# BillyBassShield.net
KiCad netlist of a schematic drawn in EAGLE
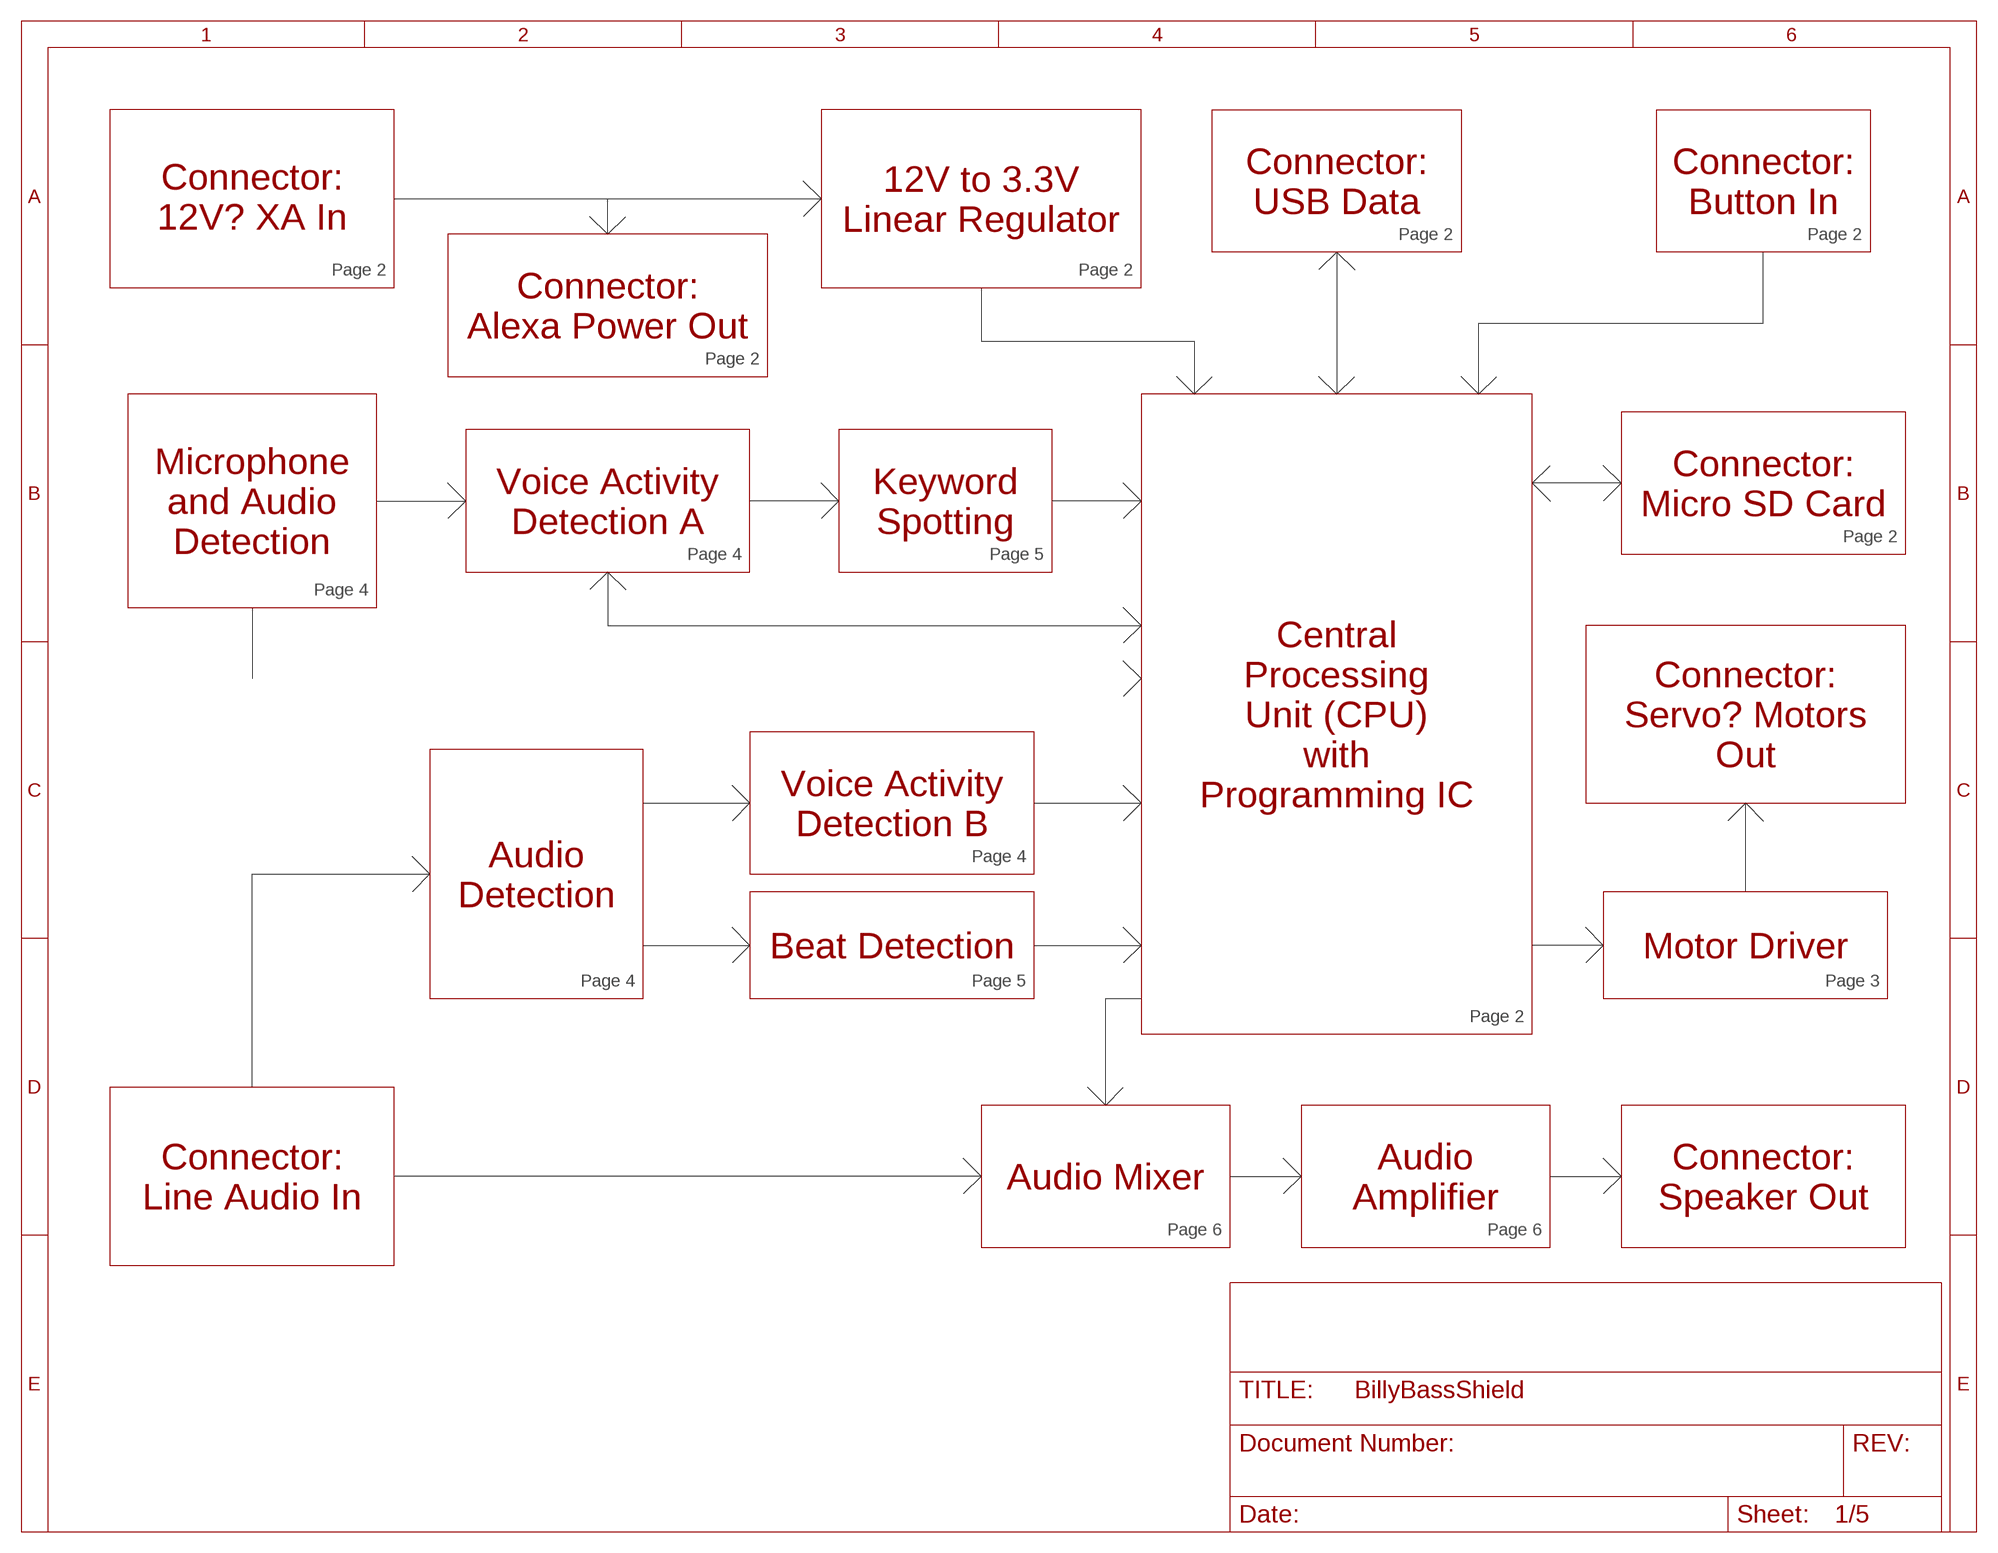
[diagram p0: schematic, sheet 1]
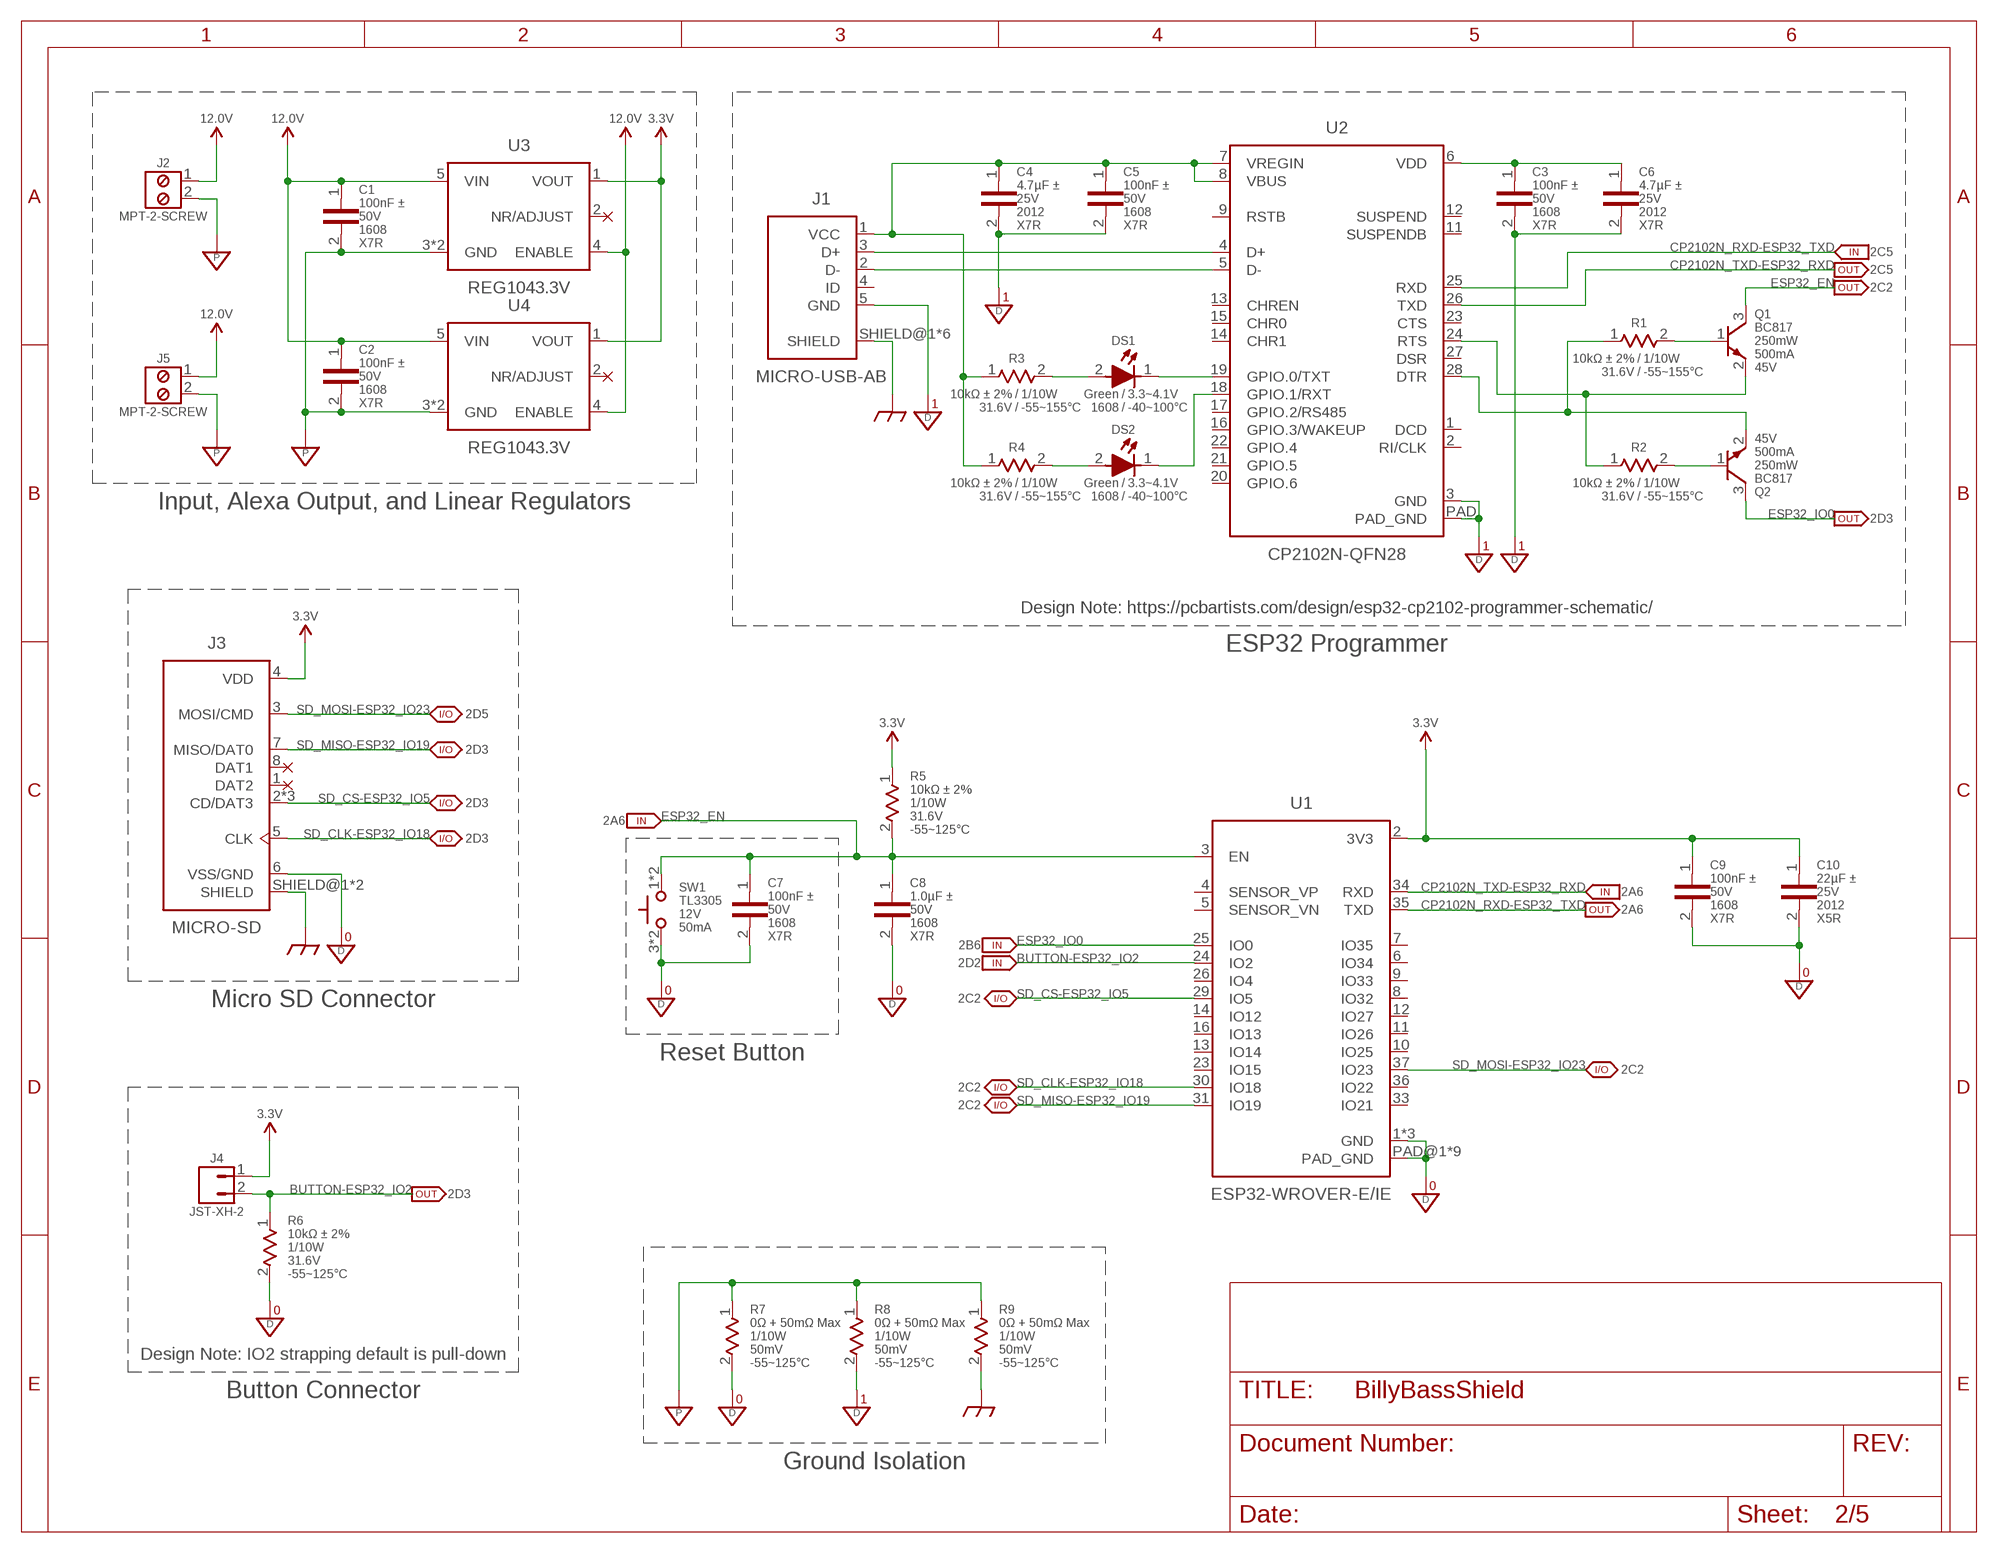
[diagram p1: schematic, sheet 2]
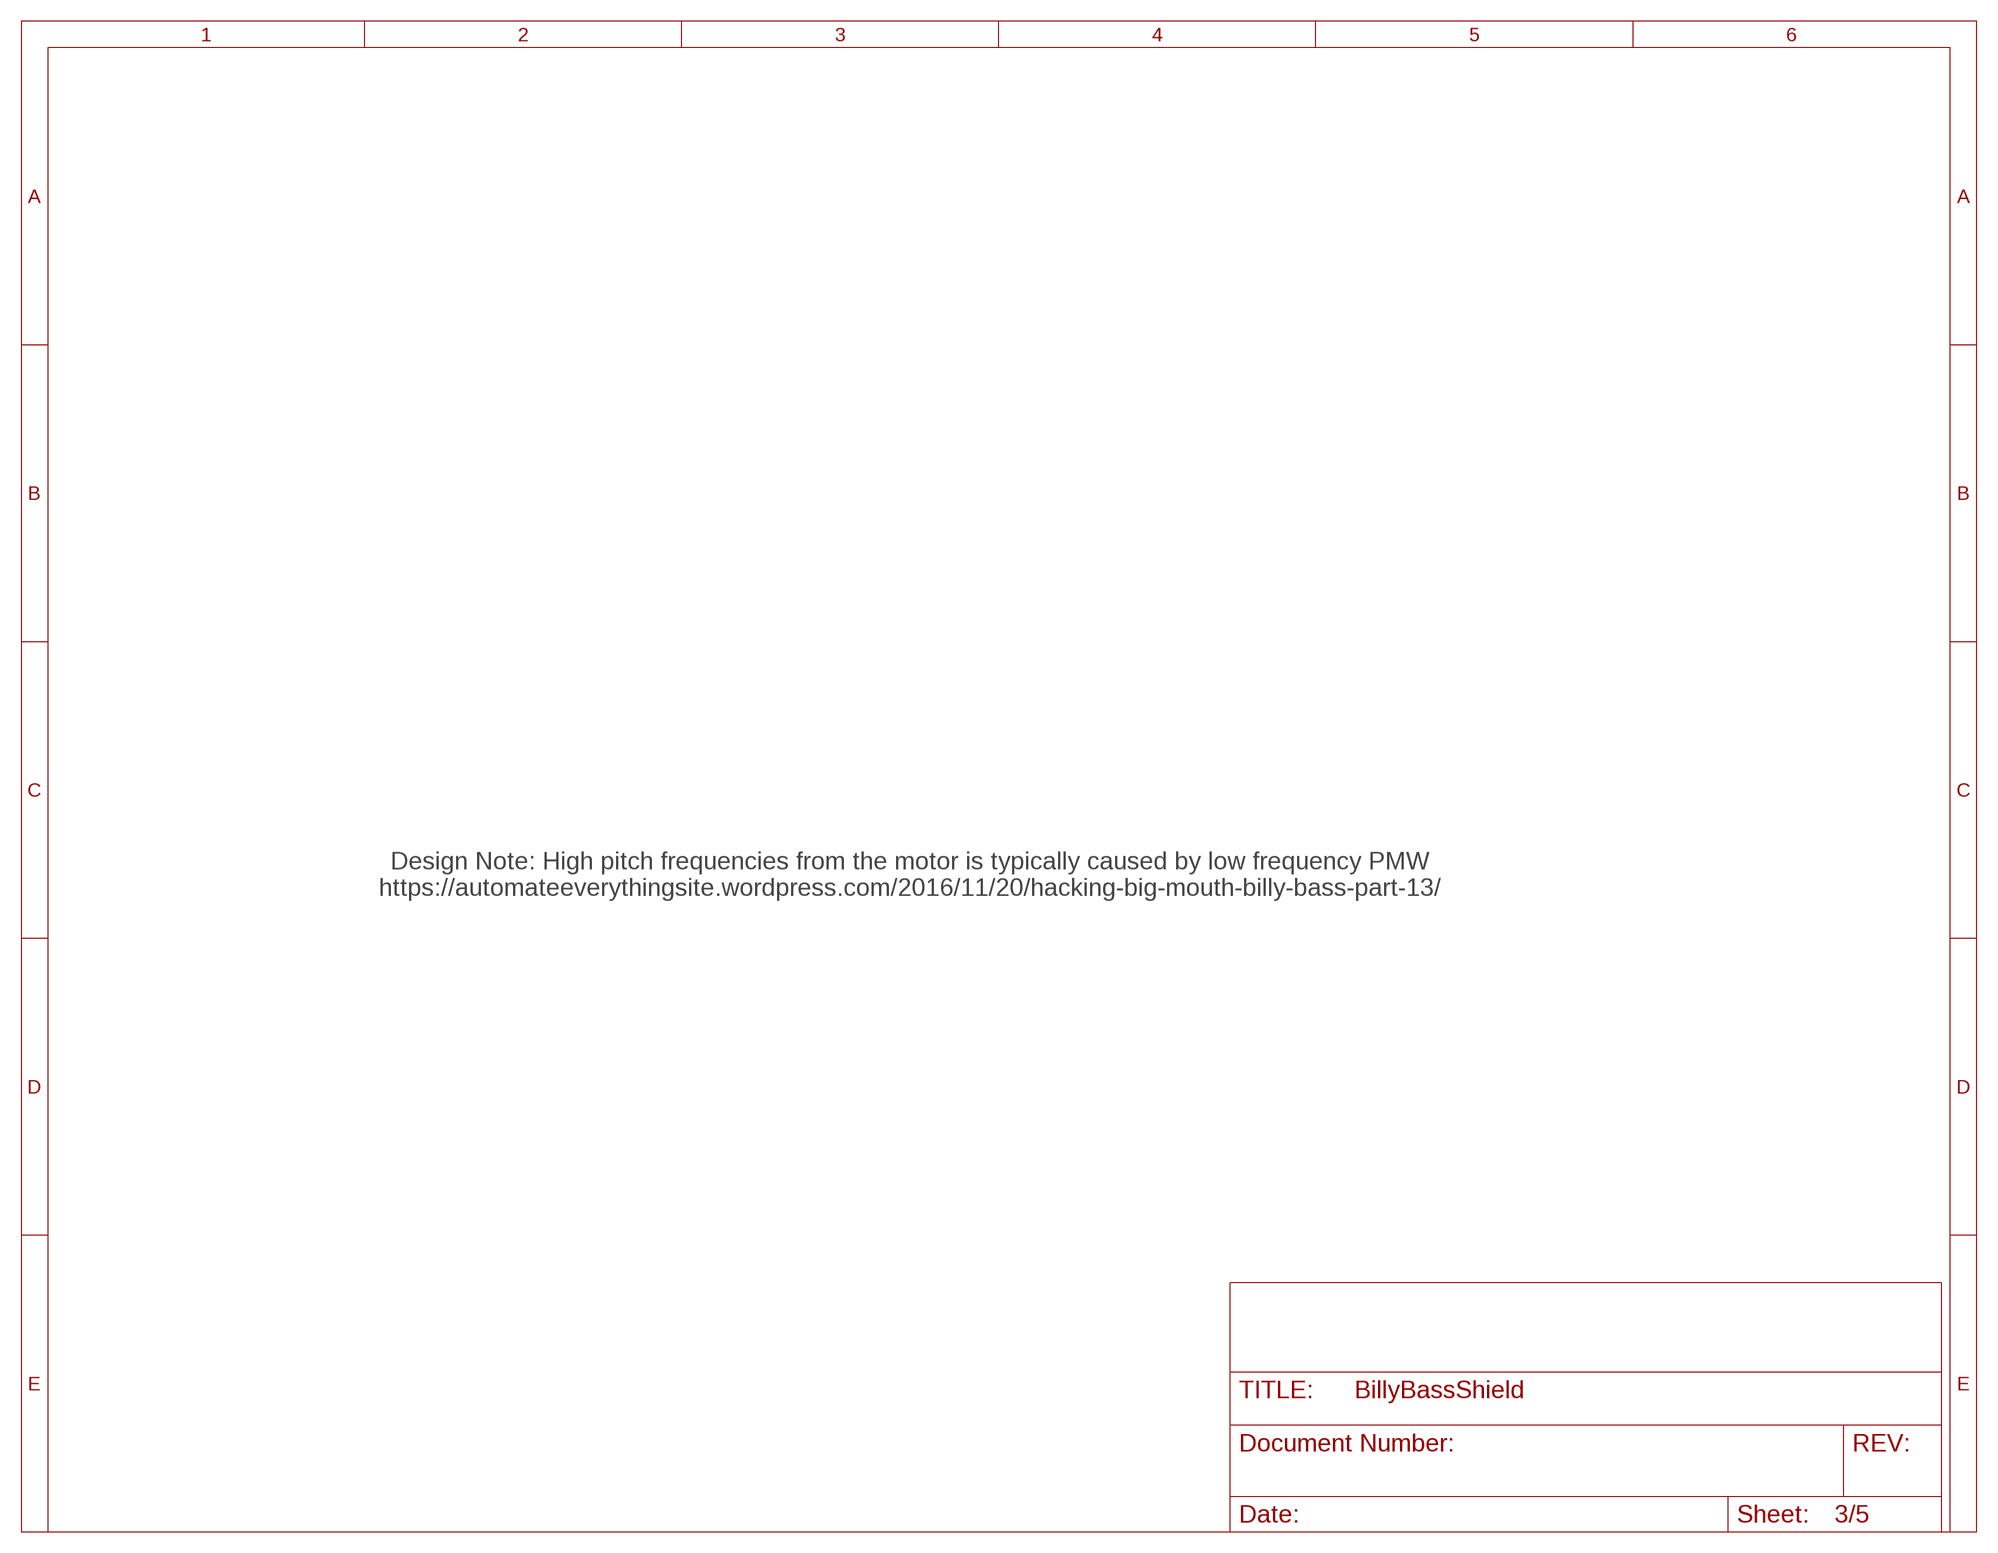
[diagram p2: schematic, sheet 3]
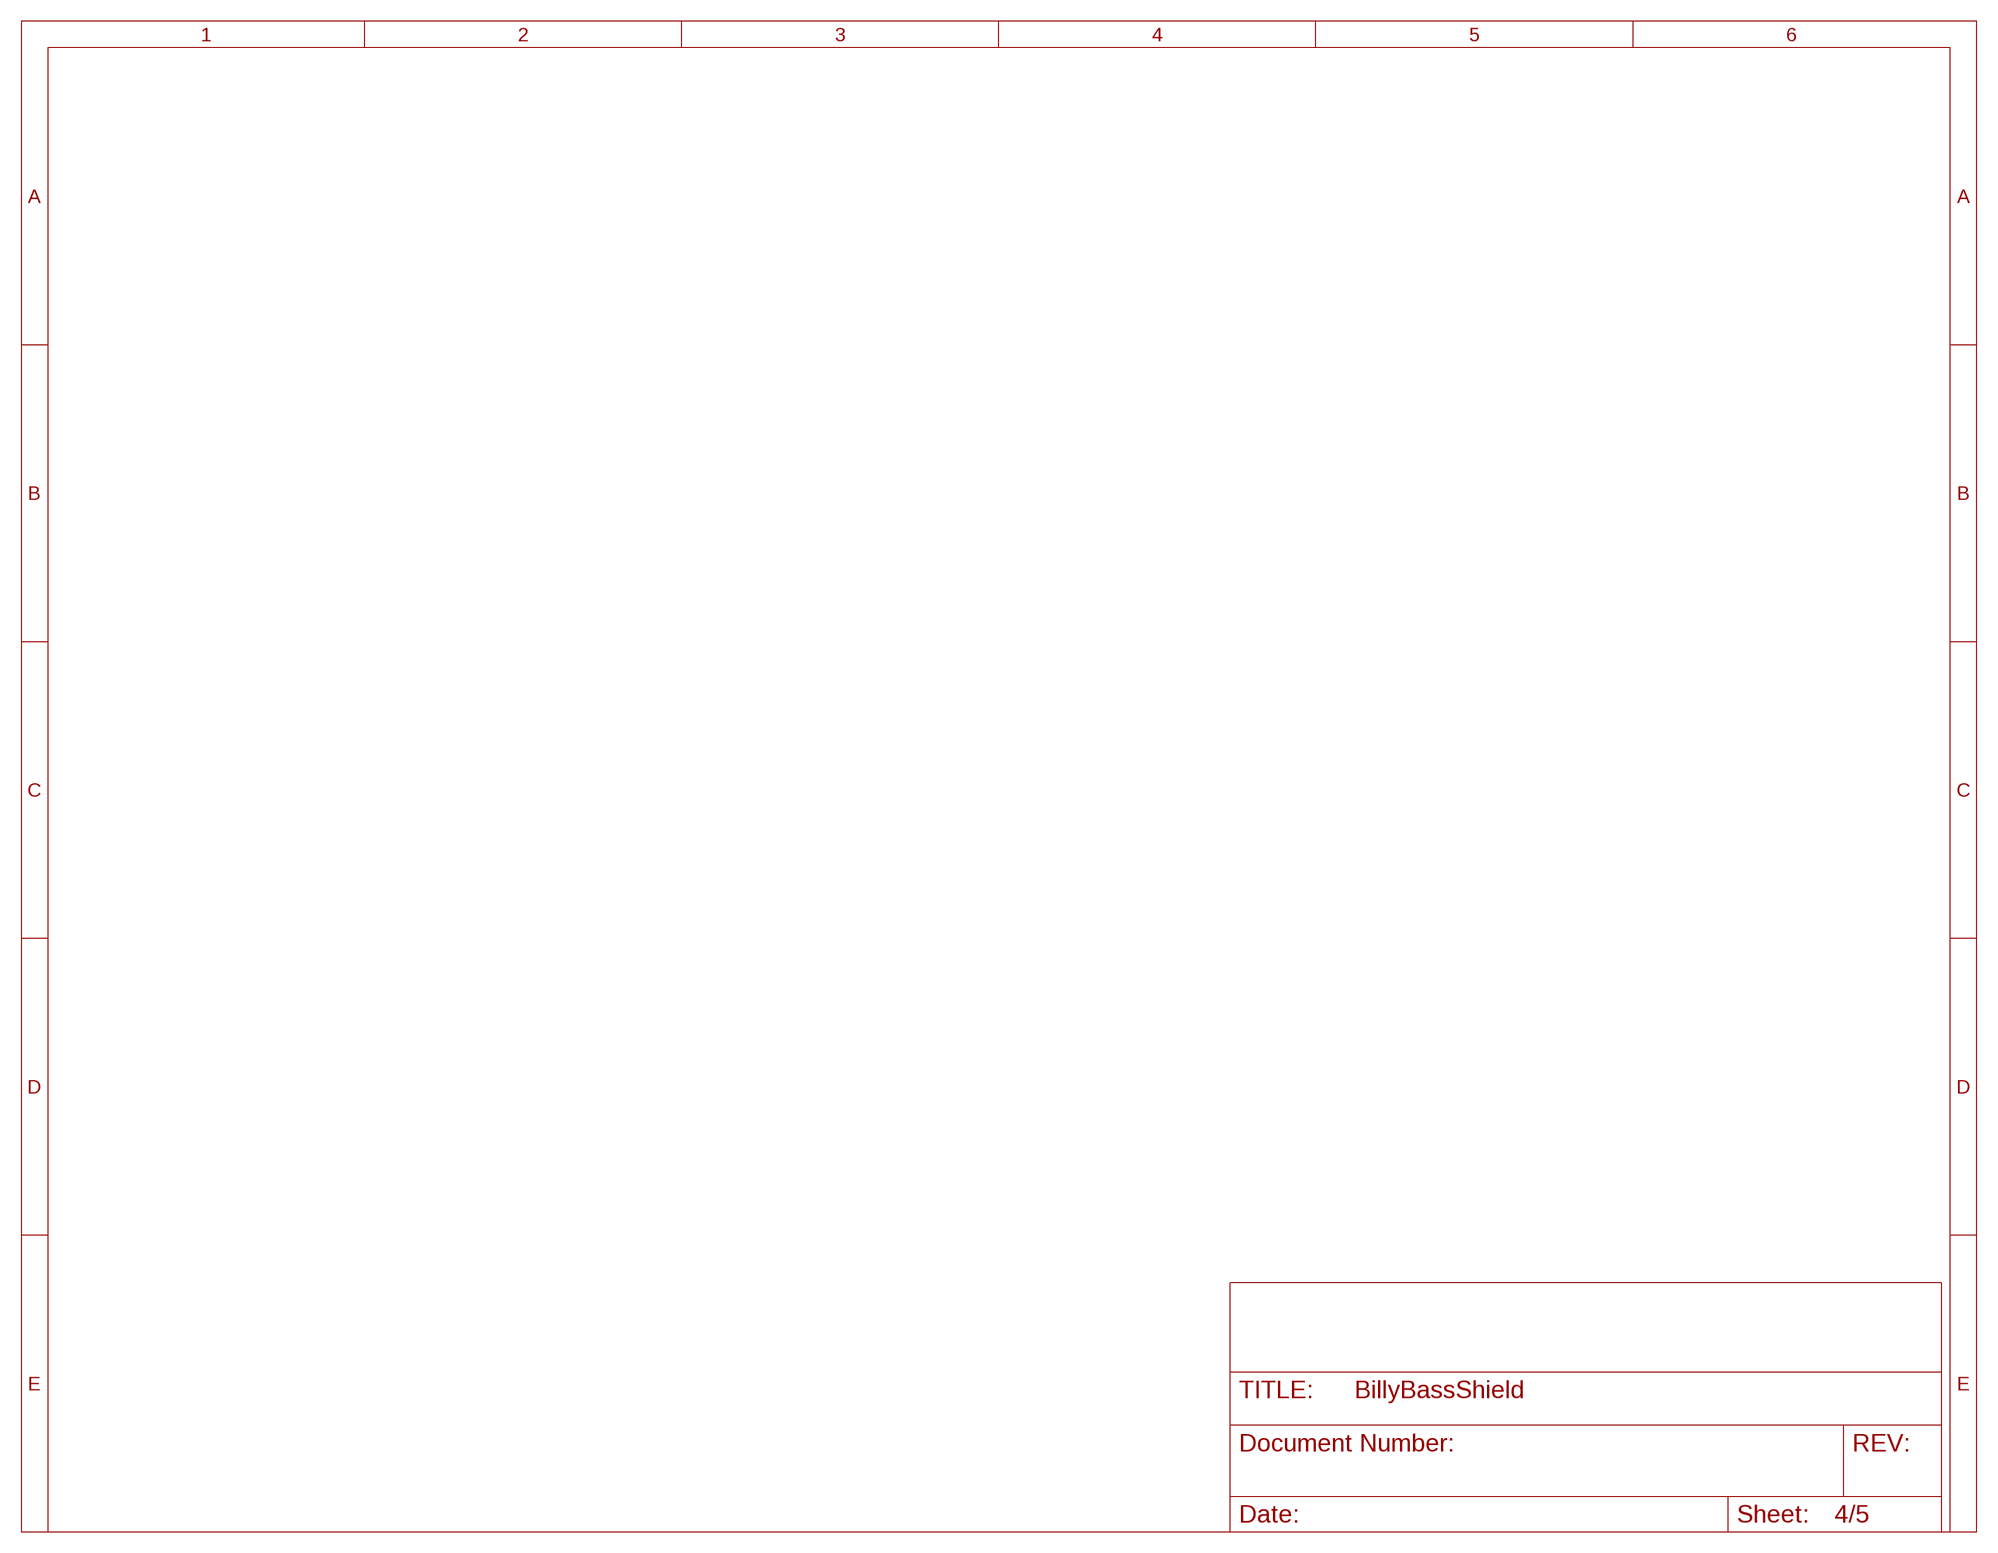
[diagram p3: schematic, sheet 4]
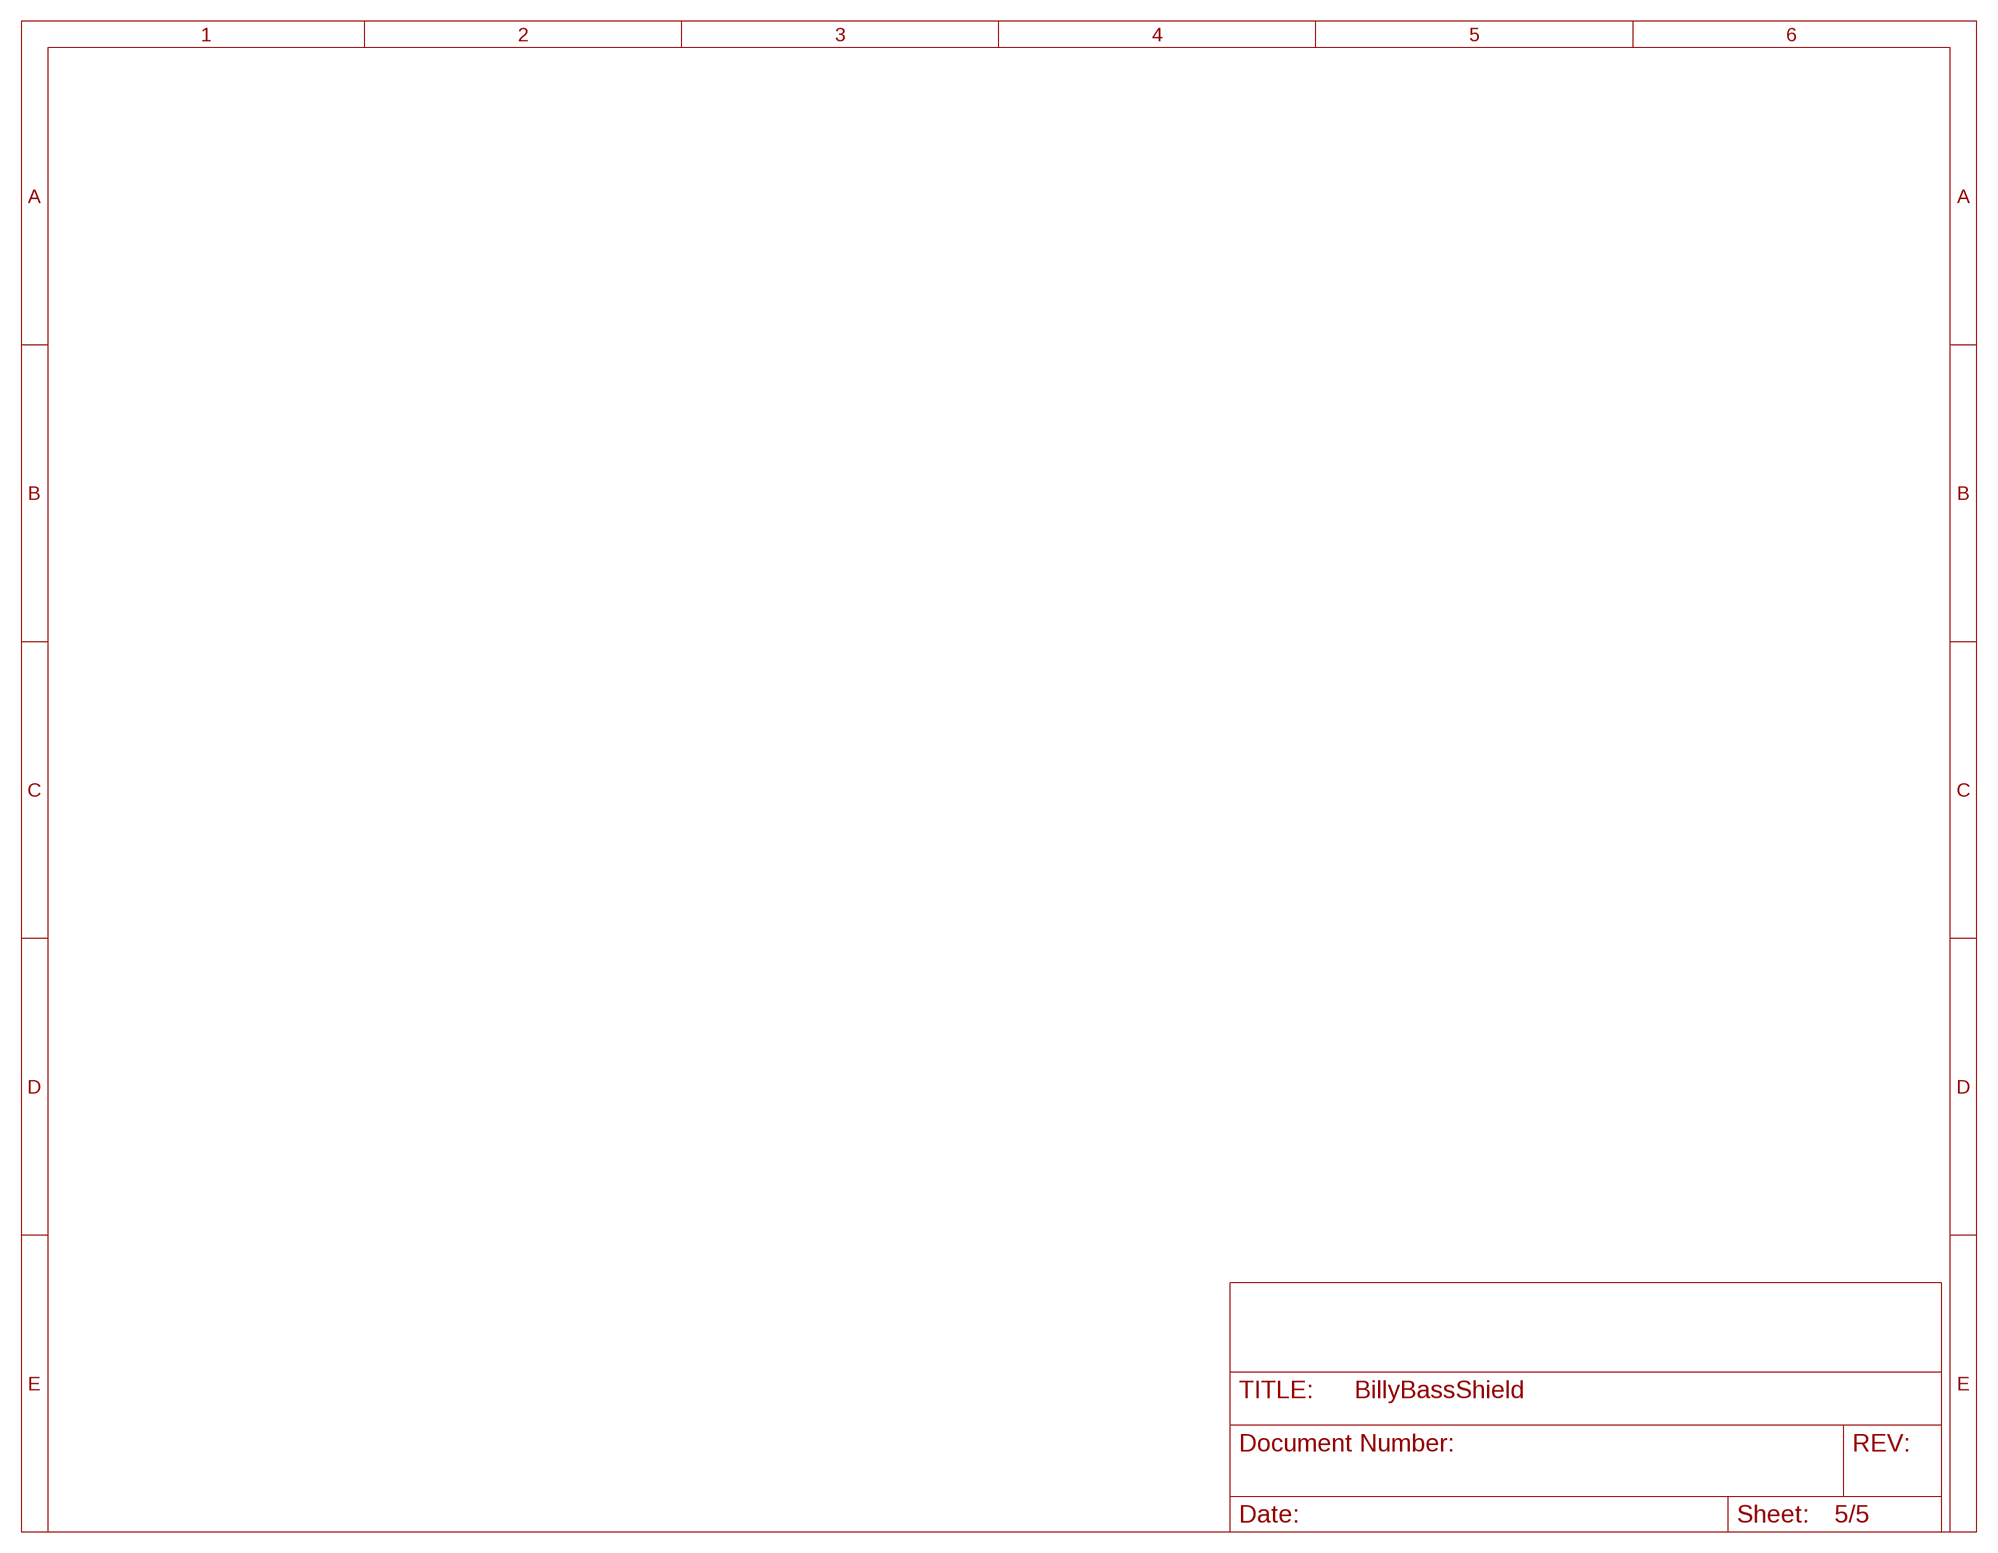
[diagram p4: schematic, sheet 5]

(export (version "E")
  (design (tool "Eeschema 10.0.6"))
  (components
    (comp (ref "C1")
      (value "100nF ±")
      (footprint "eagle-import:1608-SEM")
      (fields (field (name "SIZE") "1608") (field (name "TEMPERATURE") "X7R") (field (name "VOLTAGE") "50V"))
      (libsource (lib "eagle-import") (part "CAP-V-1608-100NF"))
    )
    (comp (ref "C2")
      (value "100nF ±")
      (footprint "eagle-import:1608-SEM")
      (fields (field (name "SIZE") "1608") (field (name "TEMPERATURE") "X7R") (field (name "VOLTAGE") "50V"))
      (libsource (lib "eagle-import") (part "CAP-V-1608-100NF"))
    )
    (comp (ref "C3")
      (value "100nF ±")
      (footprint "eagle-import:1608-SEM")
      (fields (field (name "SIZE") "1608") (field (name "TEMPERATURE") "X7R") (field (name "VOLTAGE") "50V"))
      (libsource (lib "eagle-import") (part "CAP-V-1608-100NF"))
    )
    (comp (ref "C4")
      (value "4.7µF ±")
      (footprint "eagle-import:2012-SEM")
      (fields (field (name "SIZE") "2012") (field (name "TEMPERATURE") "X7R") (field (name "VOLTAGE") "25V"))
      (libsource (lib "eagle-import") (part "CAP-V-2012-4.7UF"))
    )
    (comp (ref "C5")
      (value "100nF ±")
      (footprint "eagle-import:1608-SEM")
      (fields (field (name "SIZE") "1608") (field (name "TEMPERATURE") "X7R") (field (name "VOLTAGE") "50V"))
      (libsource (lib "eagle-import") (part "CAP-V-1608-100NF"))
    )
    (comp (ref "C6")
      (value "4.7µF ±")
      (footprint "eagle-import:2012-SEM")
      (fields (field (name "SIZE") "2012") (field (name "TEMPERATURE") "X7R") (field (name "VOLTAGE") "25V"))
      (libsource (lib "eagle-import") (part "CAP-V-2012-4.7UF"))
    )
    (comp (ref "C7")
      (value "100nF ±")
      (footprint "eagle-import:1608-SEM")
      (fields (field (name "SIZE") "1608") (field (name "TEMPERATURE") "X7R") (field (name "VOLTAGE") "50V"))
      (libsource (lib "eagle-import") (part "CAP-V-1608-100NF"))
    )
    (comp (ref "C8")
      (value "1.0µF ±")
      (footprint "eagle-import:1608-SEM")
      (fields (field (name "SIZE") "1608") (field (name "TEMPERATURE") "X7R") (field (name "VOLTAGE") "50V"))
      (libsource (lib "eagle-import") (part "CAP-V-1608-1.0UF"))
    )
    (comp (ref "C9")
      (value "100nF ±")
      (footprint "eagle-import:1608-SEM")
      (fields (field (name "SIZE") "1608") (field (name "TEMPERATURE") "X7R") (field (name "VOLTAGE") "50V"))
      (libsource (lib "eagle-import") (part "CAP-V-1608-100NF"))
    )
    (comp (ref "C10")
      (value "22µF ±")
      (footprint "eagle-import:2012-SEM")
      (fields (field (name "SIZE") "2012") (field (name "TEMPERATURE") "X5R") (field (name "VOLTAGE") "25V"))
      (libsource (lib "eagle-import") (part "CAP-V-2012-22UF"))
    )
    (comp (ref "DS1")
      (value "Green")
      (footprint "eagle-import:1608")
      (fields
        (field (name "SIZE") "1608")
        (field (name "TEMPERATURE") "-40~100°C")
        (field (name "VOLTAGE") "3.3~4.1V")
      )
      (libsource (lib "eagle-import") (part "LED-H-1608-GREEN"))
    )
    (comp (ref "DS2")
      (value "Green")
      (footprint "eagle-import:1608")
      (fields
        (field (name "SIZE") "1608")
        (field (name "TEMPERATURE") "-40~100°C")
        (field (name "VOLTAGE") "3.3~4.1V")
      )
      (libsource (lib "eagle-import") (part "LED-H-1608-GREEN"))
    )
    (comp (ref "J1")
      (value "MICRO-USB-AB")
      (footprint "eagle-import:47589-0001")
      (libsource (lib "eagle-import") (part "MICRO-USB-AB"))
    )
    (comp (ref "J2")
      (value "MPT-2-SCREW")
      (footprint "eagle-import:MPT-0.5_2-2.54")
      (libsource (lib "eagle-import") (part "MPT-2-SCREW"))
    )
    (comp (ref "J3")
      (value "MICRO-SD")
      (footprint "eagle-import:MEM2061")
      (libsource (lib "eagle-import") (part "MICRO-SD"))
    )
    (comp (ref "J4")
      (value "JST-XH-2")
      (footprint "eagle-import:B2B-XH-A")
      (libsource (lib "eagle-import") (part "JST-XH-2"))
    )
    (comp (ref "J5")
      (value "MPT-2-SCREW")
      (footprint "eagle-import:MPT-0.5_2-2.54")
      (libsource (lib "eagle-import") (part "MPT-2-SCREW"))
    )
    (comp (ref "Q1")
      (value "BC817")
      (footprint "eagle-import:SOT-23")
      (fields (field (name "POWER") "250mW") (field (name "IC_MAX") "500mA") (field (name "VCE_MAX") "45V"))
      (libsource (lib "eagle-import") (part "BJT-NPN-BC817"))
    )
    (comp (ref "Q2")
      (value "BC817")
      (footprint "eagle-import:SOT-23")
      (fields (field (name "POWER") "250mW") (field (name "IC_MAX") "500mA") (field (name "VCE_MAX") "45V"))
      (libsource (lib "eagle-import") (part "BJT-NPN-BC817"))
    )
    (comp (ref "R1")
      (value "10kΩ ± 2%")
      (footprint "eagle-import:1608-SEM")
      (fields
        (field (name "POWER") "1/10W")
        (field (name "TEMPERATURE") "-55~155°C")
        (field (name "VOLTAGE") "31.6V")
      )
      (libsource (lib "eagle-import") (part "RES-H-1608-10K"))
    )
    (comp (ref "R2")
      (value "10kΩ ± 2%")
      (footprint "eagle-import:1608-SEM")
      (fields
        (field (name "POWER") "1/10W")
        (field (name "TEMPERATURE") "-55~155°C")
        (field (name "VOLTAGE") "31.6V")
      )
      (libsource (lib "eagle-import") (part "RES-H-1608-10K"))
    )
    (comp (ref "R3")
      (value "10kΩ ± 2%")
      (footprint "eagle-import:1608-SEM")
      (fields
        (field (name "POWER") "1/10W")
        (field (name "TEMPERATURE") "-55~155°C")
        (field (name "VOLTAGE") "31.6V")
      )
      (libsource (lib "eagle-import") (part "RES-H-1608-10K"))
    )
    (comp (ref "R4")
      (value "10kΩ ± 2%")
      (footprint "eagle-import:1608-SEM")
      (fields
        (field (name "POWER") "1/10W")
        (field (name "TEMPERATURE") "-55~155°C")
        (field (name "VOLTAGE") "31.6V")
      )
      (libsource (lib "eagle-import") (part "RES-H-1608-10K"))
    )
    (comp (ref "R5")
      (value "10kΩ ± 2%")
      (footprint "eagle-import:1608-SEM")
      (fields
        (field (name "POWER") "1/10W")
        (field (name "TEMPERATURE") "-55~125°C")
        (field (name "VOLTAGE") "31.6V")
      )
      (libsource (lib "eagle-import") (part "RES-V-1608-10K"))
    )
    (comp (ref "R6")
      (value "10kΩ ± 2%")
      (footprint "eagle-import:1608-SEM")
      (fields
        (field (name "POWER") "1/10W")
        (field (name "TEMPERATURE") "-55~125°C")
        (field (name "VOLTAGE") "31.6V")
      )
      (libsource (lib "eagle-import") (part "RES-V-1608-10K"))
    )
    (comp (ref "R7")
      (value "0Ω + 50mΩ Max")
      (footprint "eagle-import:1608-SEM")
      (fields
        (field (name "POWER") "1/10W")
        (field (name "TEMPERATURE") "-55~125°C")
        (field (name "VOLTAGE") "50mV")
      )
      (libsource (lib "eagle-import") (part "RES-V-1608-0R"))
    )
    (comp (ref "R8")
      (value "0Ω + 50mΩ Max")
      (footprint "eagle-import:1608-SEM")
      (fields
        (field (name "POWER") "1/10W")
        (field (name "TEMPERATURE") "-55~125°C")
        (field (name "VOLTAGE") "50mV")
      )
      (libsource (lib "eagle-import") (part "RES-V-1608-0R"))
    )
    (comp (ref "R9")
      (value "0Ω + 50mΩ Max")
      (footprint "eagle-import:1608-SEM")
      (fields
        (field (name "POWER") "1/10W")
        (field (name "TEMPERATURE") "-55~125°C")
        (field (name "VOLTAGE") "50mV")
      )
      (libsource (lib "eagle-import") (part "RES-V-1608-0R"))
    )
    (comp (ref "SW1")
      (value "TL3305")
      (footprint "eagle-import:TL3305")
      (fields (field (name "I_MAX") "50mA") (field (name "V_MAX") "12V"))
      (libsource (lib "eagle-import") (part "BUTTON-V-SPST-TL3305"))
    )
    (comp (ref "U1")
      (value "ESP32-WROVER-E/IE")
      (footprint "eagle-import:ESP32-WROVER-E_IE")
      (libsource (lib "eagle-import") (part "ESP32-WROVER-E/IE"))
    )
    (comp (ref "U2")
      (value "CP2102N-QFN28")
      (footprint "eagle-import:QFN28")
      (libsource (lib "eagle-import") (part "CP2102N-QFN28"))
    )
    (comp (ref "U3")
      (value "REG1043.3V")
      (footprint "eagle-import:KTT")
      (libsource (lib "eagle-import") (part "REG1043.3V"))
    )
    (comp (ref "U4")
      (value "REG1043.3V")
      (footprint "eagle-import:KTT")
      (libsource (lib "eagle-import") (part "REG1043.3V"))
    )
  )
  (nets
    (net (code "1") (name "3.3V") (class "Default")
      (node (ref "C10") (pin "1") (pinfunction "P$1_1") (pintype "passive"))
      (node (ref "C9") (pin "1") (pinfunction "P$1_1") (pintype "passive"))
      (node (ref "J3") (pin "4") (pinfunction "VDD_4") (pintype "power_in"))
      (node (ref "J4") (pin "1") (pinfunction "1_1") (pintype "bidirectional"))
      (node (ref "R5") (pin "1") (pinfunction "1_1") (pintype "passive"))
      (node (ref "U1") (pin "2") (pinfunction "3V3_2") (pintype "bidirectional"))
      (node (ref "U3") (pin "1") (pinfunction "VOUT_1") (pintype "power_in"))
      (node (ref "U4") (pin "1") (pinfunction "VOUT_1") (pintype "power_in"))
    )
    (net (code "2") (name "12.0V") (class "Default")
      (node (ref "C1") (pin "1") (pinfunction "P$1_1") (pintype "passive"))
      (node (ref "C2") (pin "1") (pinfunction "P$1_1") (pintype "passive"))
      (node (ref "J2") (pin "1") (pinfunction "1_1") (pintype "bidirectional"))
      (node (ref "J5") (pin "1") (pinfunction "1_1") (pintype "bidirectional"))
      (node (ref "U3") (pin "4") (pinfunction "ENABLE_4") (pintype "input"))
      (node (ref "U3") (pin "5") (pinfunction "VIN_5") (pintype "power_in"))
      (node (ref "U4") (pin "4") (pinfunction "ENABLE_4") (pintype "input"))
      (node (ref "U4") (pin "5") (pinfunction "VIN_5") (pintype "power_in"))
    )
    (net (code "3") (name "BUTTON-ESP32_IO2") (class "Default")
      (node (ref "J4") (pin "2") (pinfunction "2_2") (pintype "bidirectional"))
      (node (ref "R6") (pin "1") (pinfunction "1_1") (pintype "passive"))
      (node (ref "U1") (pin "24") (pinfunction "IO2_24") (pintype "bidirectional"))
    )
    (net (code "4") (name "CHASSIS") (class "Default")
      (node (ref "J1") (pin "SHIELD@1") (pinfunction "SHIELD_SHIELD@1") (pintype "power_in"))
      (node (ref "J1") (pin "SHIELD@2") (pinfunction "SHIELD_SHIELD@2") (pintype "power_in"))
      (node (ref "J1") (pin "SHIELD@3") (pinfunction "SHIELD_SHIELD@3") (pintype "power_in"))
      (node (ref "J1") (pin "SHIELD@4") (pinfunction "SHIELD_SHIELD@4") (pintype "power_in"))
      (node (ref "J1") (pin "SHIELD@5") (pinfunction "SHIELD_SHIELD@5") (pintype "power_in"))
      (node (ref "J1") (pin "SHIELD@6") (pinfunction "SHIELD_SHIELD@6") (pintype "power_in"))
      (node (ref "J3") (pin "SHIELD@1") (pinfunction "SHIELD_SHIELD@1") (pintype "power_in"))
      (node (ref "J3") (pin "SHIELD@2") (pinfunction "SHIELD_SHIELD@2") (pintype "power_in"))
      (node (ref "R9") (pin "2") (pinfunction "2_2") (pintype "passive"))
    )
    (net (code "5") (name "CP2102N_RXD-ESP32_TXD") (class "Default")
      (node (ref "U1") (pin "35") (pinfunction "TXD_35") (pintype "bidirectional"))
      (node (ref "U2") (pin "25") (pinfunction "RXD_25") (pintype "bidirectional"))
    )
    (net (code "6") (name "CP2102N_TXD-ESP32_RXD") (class "Default")
      (node (ref "U1") (pin "34") (pinfunction "RXD_34") (pintype "bidirectional"))
      (node (ref "U2") (pin "26") (pinfunction "TXD_26") (pintype "bidirectional"))
    )
    (net (code "7") (name "DGND-0") (class "Default")
      (node (ref "C10") (pin "2") (pinfunction "P$2_2") (pintype "passive"))
      (node (ref "C7") (pin "2") (pinfunction "P$2_2") (pintype "passive"))
      (node (ref "C8") (pin "2") (pinfunction "P$2_2") (pintype "passive"))
      (node (ref "C9") (pin "2") (pinfunction "P$2_2") (pintype "passive"))
      (node (ref "J3") (pin "6") (pinfunction "VSS/GND_6") (pintype "power_in"))
      (node (ref "R6") (pin "2") (pinfunction "2_2") (pintype "passive"))
      (node (ref "R7") (pin "2") (pinfunction "2_2") (pintype "passive"))
      (node (ref "SW1") (pin "3") (pinfunction "1_3") (pintype "bidirectional"))
      (node (ref "SW1") (pin "4") (pinfunction "1_4") (pintype "bidirectional"))
      (node (ref "U1") (pin "1") (pinfunction "GND_1") (pintype "bidirectional"))
      (node (ref "U1") (pin "15") (pinfunction "GND_15") (pintype "bidirectional"))
      (node (ref "U1") (pin "38") (pinfunction "GND_38") (pintype "bidirectional"))
      (node (ref "U1") (pin "PAD@1") (pinfunction "PAD_GND_PAD@1") (pintype "bidirectional"))
      (node (ref "U1") (pin "PAD@2") (pinfunction "PAD_GND_PAD@2") (pintype "bidirectional"))
      (node (ref "U1") (pin "PAD@3") (pinfunction "PAD_GND_PAD@3") (pintype "bidirectional"))
      (node (ref "U1") (pin "PAD@4") (pinfunction "PAD_GND_PAD@4") (pintype "bidirectional"))
      (node (ref "U1") (pin "PAD@5") (pinfunction "PAD_GND_PAD@5") (pintype "bidirectional"))
      (node (ref "U1") (pin "PAD@6") (pinfunction "PAD_GND_PAD@6") (pintype "bidirectional"))
      (node (ref "U1") (pin "PAD@7") (pinfunction "PAD_GND_PAD@7") (pintype "bidirectional"))
      (node (ref "U1") (pin "PAD@8") (pinfunction "PAD_GND_PAD@8") (pintype "bidirectional"))
      (node (ref "U1") (pin "PAD@9") (pinfunction "PAD_GND_PAD@9") (pintype "bidirectional"))
    )
    (net (code "8") (name "DGND-1") (class "Default")
      (node (ref "C3") (pin "2") (pinfunction "P$2_2") (pintype "passive"))
      (node (ref "C4") (pin "2") (pinfunction "P$2_2") (pintype "passive"))
      (node (ref "C5") (pin "2") (pinfunction "P$2_2") (pintype "passive"))
      (node (ref "C6") (pin "2") (pinfunction "P$2_2") (pintype "passive"))
      (node (ref "J1") (pin "5") (pinfunction "GND_5") (pintype "power_in"))
      (node (ref "R8") (pin "2") (pinfunction "2_2") (pintype "passive"))
      (node (ref "U2") (pin "3") (pinfunction "GND_3") (pintype "bidirectional"))
      (node (ref "U2") (pin "PAD") (pinfunction "PAD_GND_PAD") (pintype "bidirectional"))
    )
    (net (code "9") (name "ESP32_EN") (class "Default")
      (node (ref "C7") (pin "1") (pinfunction "P$1_1") (pintype "passive"))
      (node (ref "C8") (pin "1") (pinfunction "P$1_1") (pintype "passive"))
      (node (ref "Q1") (pin "3") (pinfunction "C_3") (pintype "input"))
      (node (ref "R5") (pin "2") (pinfunction "2_2") (pintype "passive"))
      (node (ref "SW1") (pin "1") (pinfunction "2_1") (pintype "bidirectional"))
      (node (ref "SW1") (pin "2") (pinfunction "2_2") (pintype "bidirectional"))
      (node (ref "U1") (pin "3") (pinfunction "EN_3") (pintype "bidirectional"))
    )
    (net (code "10") (name "ESP32_IO0") (class "Default")
      (node (ref "Q2") (pin "3") (pinfunction "C_3") (pintype "input"))
      (node (ref "U1") (pin "25") (pinfunction "IO0_25") (pintype "bidirectional"))
    )
    (net (code "11") (name "Net-(C3-P$1)") (class "Default")
      (node (ref "C3") (pin "1") (pinfunction "P$1_1") (pintype "passive"))
      (node (ref "C6") (pin "1") (pinfunction "P$1_1") (pintype "passive"))
      (node (ref "U2") (pin "6") (pinfunction "VDD_6") (pintype "bidirectional"))
    )
    (net (code "12") (name "Net-(C4-P$1)") (class "Default")
      (node (ref "C4") (pin "1") (pinfunction "P$1_1") (pintype "passive"))
      (node (ref "C5") (pin "1") (pinfunction "P$1_1") (pintype "passive"))
      (node (ref "J1") (pin "1") (pinfunction "VCC_1") (pintype "power_in"))
      (node (ref "R3") (pin "1") (pinfunction "1_1") (pintype "passive"))
      (node (ref "R4") (pin "1") (pinfunction "1_1") (pintype "passive"))
      (node (ref "U2") (pin "7") (pinfunction "VREGIN_7") (pintype "bidirectional"))
      (node (ref "U2") (pin "8") (pinfunction "VBUS_8") (pintype "bidirectional"))
    )
    (net (code "13") (name "Net-(DS1-Pad2)") (class "Default")
      (node (ref "DS1") (pin "2") (pinfunction "2_2") (pintype "input"))
      (node (ref "R3") (pin "2") (pinfunction "2_2") (pintype "passive"))
    )
    (net (code "14") (name "Net-(DS2-Pad2)") (class "Default")
      (node (ref "DS2") (pin "2") (pinfunction "2_2") (pintype "input"))
      (node (ref "R4") (pin "2") (pinfunction "2_2") (pintype "passive"))
    )
    (net (code "15") (name "Net-(J1-D+)") (class "Default")
      (node (ref "J1") (pin "3") (pinfunction "D+_3") (pintype "input"))
      (node (ref "U2") (pin "4") (pinfunction "D+_4") (pintype "bidirectional"))
    )
    (net (code "16") (name "Net-(J1-D-)") (class "Default")
      (node (ref "J1") (pin "2") (pinfunction "D-_2") (pintype "output"))
      (node (ref "U2") (pin "5") (pinfunction "D-_5") (pintype "bidirectional"))
    )
    (net (code "17") (name "Net-(Q1-B)") (class "Default")
      (node (ref "Q1") (pin "1") (pinfunction "B_1") (pintype "input"))
      (node (ref "R1") (pin "2") (pinfunction "2_2") (pintype "passive"))
    )
    (net (code "18") (name "Net-(Q1-E)") (class "Default")
      (node (ref "Q1") (pin "2") (pinfunction "E_2") (pintype "output"))
      (node (ref "R2") (pin "1") (pinfunction "1_1") (pintype "passive"))
      (node (ref "U2") (pin "24") (pinfunction "RTS_24") (pintype "bidirectional"))
    )
    (net (code "19") (name "Net-(Q2-B)") (class "Default")
      (node (ref "Q2") (pin "1") (pinfunction "B_1") (pintype "input"))
      (node (ref "R2") (pin "2") (pinfunction "2_2") (pintype "passive"))
    )
    (net (code "20") (name "Net-(Q2-E)") (class "Default")
      (node (ref "Q2") (pin "2") (pinfunction "E_2") (pintype "output"))
      (node (ref "R1") (pin "1") (pinfunction "1_1") (pintype "passive"))
      (node (ref "U2") (pin "28") (pinfunction "DTR_28") (pintype "bidirectional"))
    )
    (net (code "21") (name "Net-(U2-GPIO.0{slash}TXT)") (class "Default")
      (node (ref "DS1") (pin "1") (pinfunction "1_1") (pintype "output"))
      (node (ref "U2") (pin "19") (pinfunction "GPIO.0/TXT_19") (pintype "bidirectional"))
    )
    (net (code "22") (name "Net-(U2-GPIO.1{slash}RXT)") (class "Default")
      (node (ref "DS2") (pin "1") (pinfunction "1_1") (pintype "output"))
      (node (ref "U2") (pin "18") (pinfunction "GPIO.1/RXT_18") (pintype "bidirectional"))
    )
    (net (code "23") (name "PGND") (class "Default")
      (node (ref "C1") (pin "2") (pinfunction "P$2_2") (pintype "passive"))
      (node (ref "C2") (pin "2") (pinfunction "P$2_2") (pintype "passive"))
      (node (ref "J2") (pin "2") (pinfunction "2_2") (pintype "bidirectional"))
      (node (ref "J5") (pin "2") (pinfunction "2_2") (pintype "bidirectional"))
      (node (ref "R7") (pin "1") (pinfunction "1_1") (pintype "passive"))
      (node (ref "R8") (pin "1") (pinfunction "1_1") (pintype "passive"))
      (node (ref "R9") (pin "1") (pinfunction "1_1") (pintype "passive"))
      (node (ref "U3") (pin "3") (pinfunction "GND_3") (pintype "bidirectional"))
      (node (ref "U3") (pin "PAD") (pinfunction "GND_PAD") (pintype "bidirectional"))
      (node (ref "U4") (pin "3") (pinfunction "GND_3") (pintype "bidirectional"))
      (node (ref "U4") (pin "PAD") (pinfunction "GND_PAD") (pintype "bidirectional"))
    )
    (net (code "24") (name "SD_CLK-ESP32_IO18") (class "Default")
      (node (ref "J3") (pin "5") (pinfunction "CLK_5") (pintype "input"))
      (node (ref "U1") (pin "30") (pinfunction "IO18_30") (pintype "bidirectional"))
    )
    (net (code "25") (name "SD_CS-ESP32_IO5") (class "Default")
      (node (ref "J3") (pin "2") (pinfunction "CD/DAT3_2") (pintype "bidirectional"))
      (node (ref "J3") (pin "CD@1") (pinfunction "CD/DAT3_CD@1") (pintype "bidirectional"))
      (node (ref "J3") (pin "CD@2") (pinfunction "CD/DAT3_CD@2") (pintype "bidirectional"))
      (node (ref "U1") (pin "29") (pinfunction "IO5_29") (pintype "bidirectional"))
    )
    (net (code "26") (name "SD_MISO-ESP32_IO19") (class "Default")
      (node (ref "J3") (pin "7") (pinfunction "MISO/DAT0_7") (pintype "bidirectional"))
      (node (ref "U1") (pin "31") (pinfunction "IO19_31") (pintype "bidirectional"))
    )
    (net (code "27") (name "SD_MOSI-ESP32_IO23") (class "Default")
      (node (ref "J3") (pin "3") (pinfunction "MOSI/CMD_3") (pintype "input"))
      (node (ref "U1") (pin "37") (pinfunction "IO23_37") (pintype "bidirectional"))
    )
    (net (code "28") (name "unconnected-(J1-ID-Pad4)") (class "Default")
      (node (ref "J1") (pin "4") (pinfunction "ID_4") (pintype "no_connect"))
    )
    (net (code "29") (name "unconnected-(J3-DAT1-Pad8)") (class "Default")
      (node (ref "J3") (pin "8") (pinfunction "DAT1_8") (pintype "bidirectional"))
    )
    (net (code "30") (name "unconnected-(J3-DAT2-Pad1)") (class "Default")
      (node (ref "J3") (pin "1") (pinfunction "DAT2_1") (pintype "bidirectional"))
    )
    (net (code "31") (name "unconnected-(U1-IO4-Pad26)") (class "Default")
      (node (ref "U1") (pin "26") (pinfunction "IO4_26") (pintype "bidirectional"))
    )
    (net (code "32") (name "unconnected-(U1-IO12-Pad14)") (class "Default")
      (node (ref "U1") (pin "14") (pinfunction "IO12_14") (pintype "bidirectional"))
    )
    (net (code "33") (name "unconnected-(U1-IO13-Pad16)") (class "Default")
      (node (ref "U1") (pin "16") (pinfunction "IO13_16") (pintype "bidirectional"))
    )
    (net (code "34") (name "unconnected-(U1-IO14-Pad13)") (class "Default")
      (node (ref "U1") (pin "13") (pinfunction "IO14_13") (pintype "bidirectional"))
    )
    (net (code "35") (name "unconnected-(U1-IO15-Pad23)") (class "Default")
      (node (ref "U1") (pin "23") (pinfunction "IO15_23") (pintype "bidirectional"))
    )
    (net (code "36") (name "unconnected-(U1-IO21-Pad33)") (class "Default")
      (node (ref "U1") (pin "33") (pinfunction "IO21_33") (pintype "bidirectional"))
    )
    (net (code "37") (name "unconnected-(U1-IO22-Pad36)") (class "Default")
      (node (ref "U1") (pin "36") (pinfunction "IO22_36") (pintype "bidirectional"))
    )
    (net (code "38") (name "unconnected-(U1-IO25-Pad10)") (class "Default")
      (node (ref "U1") (pin "10") (pinfunction "IO25_10") (pintype "bidirectional"))
    )
    (net (code "39") (name "unconnected-(U1-IO26-Pad11)") (class "Default")
      (node (ref "U1") (pin "11") (pinfunction "IO26_11") (pintype "bidirectional"))
    )
    (net (code "40") (name "unconnected-(U1-IO27-Pad12)") (class "Default")
      (node (ref "U1") (pin "12") (pinfunction "IO27_12") (pintype "bidirectional"))
    )
    (net (code "41") (name "unconnected-(U1-IO32-Pad8)") (class "Default")
      (node (ref "U1") (pin "8") (pinfunction "IO32_8") (pintype "bidirectional"))
    )
    (net (code "42") (name "unconnected-(U1-IO33-Pad9)") (class "Default")
      (node (ref "U1") (pin "9") (pinfunction "IO33_9") (pintype "bidirectional"))
    )
    (net (code "43") (name "unconnected-(U1-IO34-Pad6)") (class "Default")
      (node (ref "U1") (pin "6") (pinfunction "IO34_6") (pintype "bidirectional"))
    )
    (net (code "44") (name "unconnected-(U1-IO35-Pad7)") (class "Default")
      (node (ref "U1") (pin "7") (pinfunction "IO35_7") (pintype "bidirectional"))
    )
    (net (code "45") (name "unconnected-(U1-SENSOR_VN-Pad5)") (class "Default")
      (node (ref "U1") (pin "5") (pinfunction "SENSOR_VN_5") (pintype "bidirectional"))
    )
    (net (code "46") (name "unconnected-(U1-SENSOR_VP-Pad4)") (class "Default")
      (node (ref "U1") (pin "4") (pinfunction "SENSOR_VP_4") (pintype "bidirectional"))
    )
    (net (code "47") (name "unconnected-(U2-CHR0-Pad15)") (class "Default")
      (node (ref "U2") (pin "15") (pinfunction "CHR0_15") (pintype "bidirectional"))
    )
    (net (code "48") (name "unconnected-(U2-CHR1-Pad14)") (class "Default")
      (node (ref "U2") (pin "14") (pinfunction "CHR1_14") (pintype "bidirectional"))
    )
    (net (code "49") (name "unconnected-(U2-CHREN-Pad13)") (class "Default")
      (node (ref "U2") (pin "13") (pinfunction "CHREN_13") (pintype "bidirectional"))
    )
    (net (code "50") (name "unconnected-(U2-CTS-Pad23)") (class "Default")
      (node (ref "U2") (pin "23") (pinfunction "CTS_23") (pintype "bidirectional"))
    )
    (net (code "51") (name "unconnected-(U2-DCD-Pad1)") (class "Default")
      (node (ref "U2") (pin "1") (pinfunction "DCD_1") (pintype "bidirectional"))
    )
    (net (code "52") (name "unconnected-(U2-DSR-Pad27)") (class "Default")
      (node (ref "U2") (pin "27") (pinfunction "DSR_27") (pintype "bidirectional"))
    )
    (net (code "53") (name "unconnected-(U2-GPIO.2{slash}RS485-Pad17)") (class "Default")
      (node (ref "U2") (pin "17") (pinfunction "GPIO.2/RS485_17") (pintype "bidirectional"))
    )
    (net (code "54") (name "unconnected-(U2-GPIO.3{slash}WAKEUP-Pad16)") (class "Default")
      (node (ref "U2") (pin "16") (pinfunction "GPIO.3/WAKEUP_16") (pintype "bidirectional"))
    )
    (net (code "55") (name "unconnected-(U2-GPIO.4-Pad22)") (class "Default")
      (node (ref "U2") (pin "22") (pinfunction "GPIO.4_22") (pintype "bidirectional"))
    )
    (net (code "56") (name "unconnected-(U2-GPIO.5-Pad21)") (class "Default")
      (node (ref "U2") (pin "21") (pinfunction "GPIO.5_21") (pintype "bidirectional"))
    )
    (net (code "57") (name "unconnected-(U2-GPIO.6-Pad20)") (class "Default")
      (node (ref "U2") (pin "20") (pinfunction "GPIO.6_20") (pintype "bidirectional"))
    )
    (net (code "58") (name "unconnected-(U2-RI{slash}CLK-Pad2)") (class "Default")
      (node (ref "U2") (pin "2") (pinfunction "RI/CLK_2") (pintype "bidirectional"))
    )
    (net (code "59") (name "unconnected-(U2-RSTB-Pad9)") (class "Default")
      (node (ref "U2") (pin "9") (pinfunction "RSTB_9") (pintype "bidirectional"))
    )
    (net (code "60") (name "unconnected-(U2-SUSPEND-Pad12)") (class "Default")
      (node (ref "U2") (pin "12") (pinfunction "SUSPEND_12") (pintype "bidirectional"))
    )
    (net (code "61") (name "unconnected-(U2-SUSPENDB-Pad11)") (class "Default")
      (node (ref "U2") (pin "11") (pinfunction "SUSPENDB_11") (pintype "bidirectional"))
    )
    (net (code "62") (name "unconnected-(U3-NR{slash}ADJUST-Pad2)") (class "Default")
      (node (ref "U3") (pin "2") (pinfunction "NR/ADJUST_2") (pintype "bidirectional"))
    )
    (net (code "63") (name "unconnected-(U4-NR{slash}ADJUST-Pad2)") (class "Default")
      (node (ref "U4") (pin "2") (pinfunction "NR/ADJUST_2") (pintype "bidirectional"))
    )
  )
)
